# 1_-MCU.net
KiCad netlist of a schematic drawn in Altium Designer
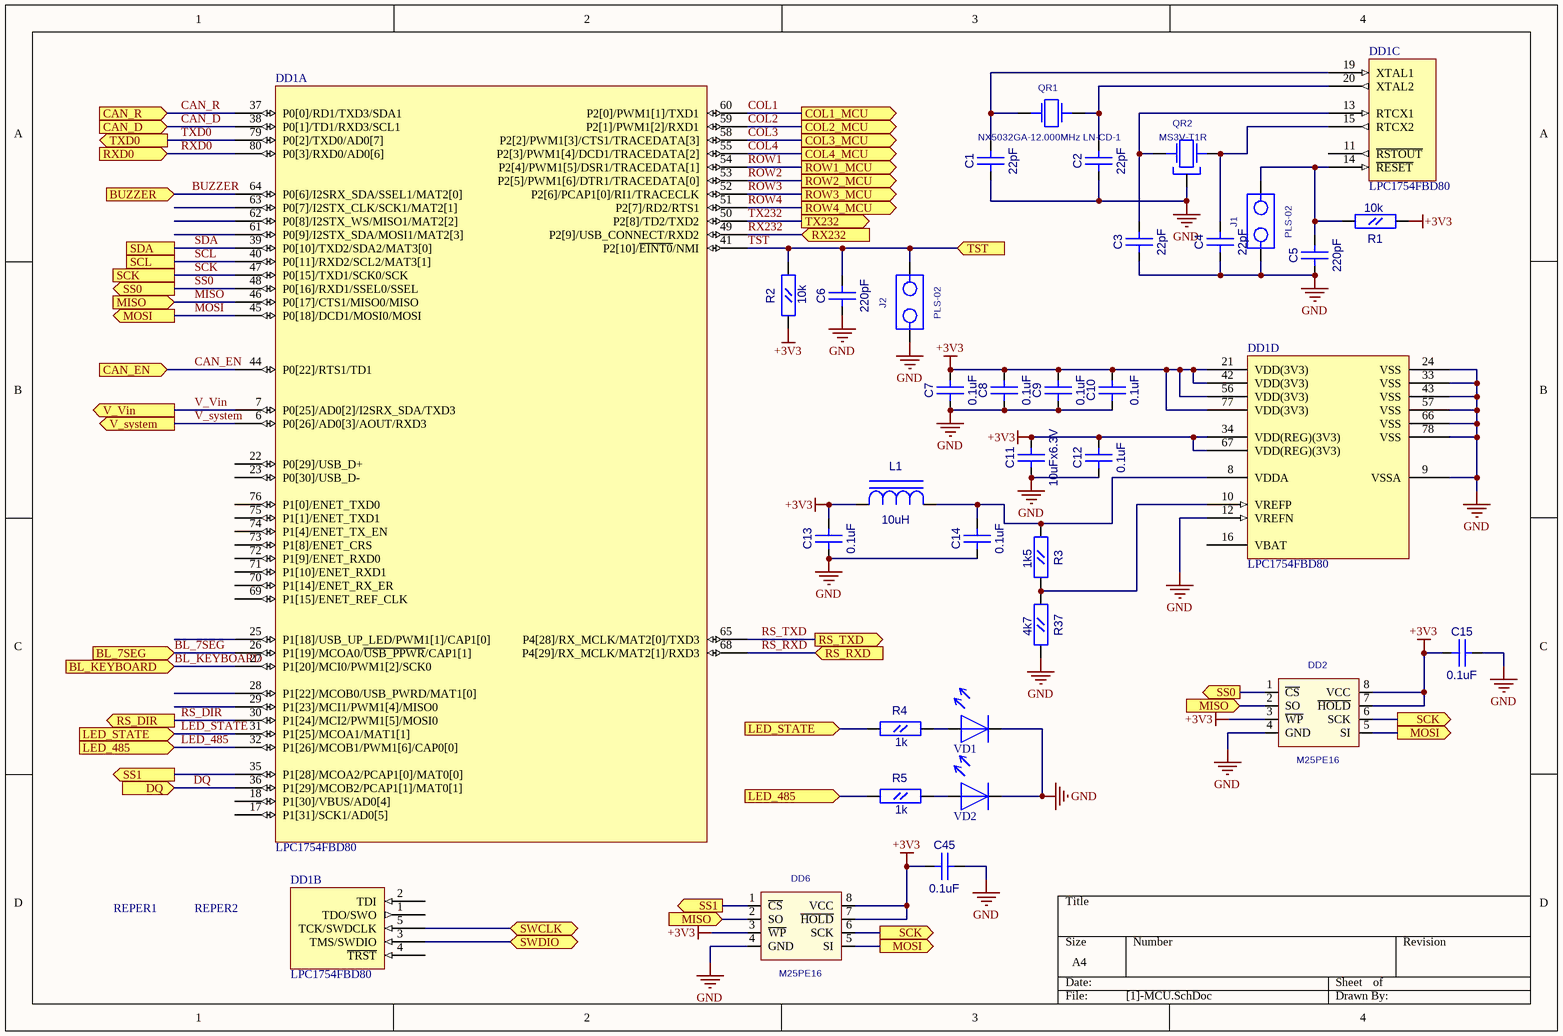
[diagram p0: [1]-MCU.SchDoc]

(export (version "E")
  (design (tool "Eeschema 10.0.6"))
  (components
    (comp (ref "C1")
      (value "22pF")
      (footprint "CC0603")
      (description "CC0603")
      (libsource (lib "gprs_modem_2") (part "CC0603"))
    )
    (comp (ref "C2")
      (value "22pF")
      (footprint "CC0603")
      (description "CC0603")
      (libsource (lib "gprs_modem_2") (part "CC0603"))
    )
    (comp (ref "C3")
      (value "22pF")
      (footprint "CC0603")
      (description "CC0603")
      (libsource (lib "gprs_modem_2") (part "CC0603"))
    )
    (comp (ref "C4")
      (value "22pF")
      (footprint "CC0603")
      (description "CC0603")
      (libsource (lib "gprs_modem_2") (part "CC0603"))
    )
    (comp (ref "C5")
      (value "220pF")
      (footprint "CC0603")
      (description "CC0603")
      (libsource (lib "gprs_modem_2") (part "CC0603"))
    )
    (comp (ref "C6")
      (value "220pF")
      (footprint "CC0603")
      (description "CC0603")
      (libsource (lib "gprs_modem_2") (part "CC0603"))
    )
    (comp (ref "C7")
      (value "0.1uF")
      (footprint "CC0603")
      (description "CC0603")
      (libsource (lib "gprs_modem_2") (part "CC0603"))
    )
    (comp (ref "C8")
      (value "0.1uF")
      (footprint "CC0603")
      (description "CC0603")
      (libsource (lib "gprs_modem_2") (part "CC0603"))
    )
    (comp (ref "C9")
      (value "0.1uF")
      (footprint "CC0603")
      (description "CC0603")
      (libsource (lib "gprs_modem_2") (part "CC0603"))
    )
    (comp (ref "C10")
      (value "0.1uF")
      (footprint "CC0603")
      (description "CC0603")
      (libsource (lib "gprs_modem_2") (part "CC0603"))
    )
    (comp (ref "C11")
      (value "10uFx6.3V")
      (footprint "CC0805")
      (description "CC0805")
      (libsource (lib "gprs_modem_2") (part "CC0805"))
    )
    (comp (ref "C12")
      (value "0.1uF")
      (footprint "CC0603")
      (description "CC0603")
      (libsource (lib "gprs_modem_2") (part "CC0603"))
    )
    (comp (ref "C13")
      (value "0.1uF")
      (footprint "CC0603")
      (description "CC0603")
      (libsource (lib "gprs_modem_2") (part "CC0603"))
    )
    (comp (ref "C14")
      (value "0.1uF")
      (footprint "CC0603")
      (description "CC0603")
      (libsource (lib "gprs_modem_2") (part "CC0603"))
    )
    (comp (ref "C15")
      (value "0.1uF")
      (footprint "CC0603")
      (description "CC0603")
      (libsource (lib "gprs_modem_2") (part "CC0603"))
    )
    (comp (ref "C45")
      (value "0.1uF")
      (footprint "CC0603")
      (description "CC0603")
      (libsource (lib "gprs_modem_2") (part "CC0603"))
    )
    (comp (ref "DD1")
      (value "LPC1754FBD80")
      (footprint "TQFP-80_0.5")
      (description "Cortex -M3 32-Bit Microcontroller, 128KB Flash, 64KB RAM, 800-Lead LQFP")
      (libsource (lib "gprs_modem_2") (part "LPC1754FBD80"))
    )
    (comp (ref "DD2")
      (value "M25PE16")
      (footprint "EIAJ_SO8")
      (description "S25FL016A0LMFI01")
      (libsource (lib "gprs_modem_2") (part "S25FL016A0LMFI01"))
    )
    (comp (ref "DD6")
      (value "M25PE16")
      (footprint "EIAJ_SO8")
      (description "S25FL016A0LMFI01")
      (libsource (lib "gprs_modem_2") (part "S25FL016A0LMFI01"))
    )
    (comp (ref "J1") (value "PLS-02") (footprint "PLS-02") (libsource (lib "gprs_modem_2") (part "PLS-02")))
    (comp (ref "J2") (value "PLS-02") (footprint "PLS-02") (libsource (lib "gprs_modem_2") (part "PLS-02")))
    (comp (ref "L1")
      (value "10uH")
      (footprint "L0603")
      (description "L0603")
      (libsource (lib "gprs_modem_2") (part "L0603"))
    )
    (comp (ref "QR1")
      (value "NX5032GA-12.000MHz LN-CD-1")
      (footprint "AC5032_2")
      (description "AC5032/2")
      (libsource (lib "gprs_modem_2") (part "AC5032_2"))
    )
    (comp (ref "QR2")
      (value "MS3V-T1R")
      (footprint "MS3V-T1R")
      (description "CRYSTAL_32768 Hz")
      (libsource (lib "gprs_modem_2") (part "MS3V-T1R"))
    )
    (comp (ref "R1")
      (value "10k")
      (footprint "RC0603")
      (description "RC0603")
      (libsource (lib "gprs_modem_2") (part "RC0603"))
    )
    (comp (ref "R2")
      (value "10k")
      (footprint "RC0603")
      (description "RC0603")
      (libsource (lib "gprs_modem_2") (part "RC0603"))
    )
    (comp (ref "R3")
      (value "1k5")
      (footprint "RC0603")
      (description "RC0603")
      (libsource (lib "gprs_modem_2") (part "RC0603"))
    )
    (comp (ref "R4")
      (value "1k")
      (footprint "RC0603")
      (description "RC0603")
      (libsource (lib "gprs_modem_2") (part "RC0603"))
    )
    (comp (ref "R5")
      (value "1k")
      (footprint "RC0603")
      (description "RC0603")
      (libsource (lib "gprs_modem_2") (part "RC0603"))
    )
    (comp (ref "R37")
      (value "4k7")
      (footprint "RC0603")
      (description "RC0603")
      (libsource (lib "gprs_modem_2") (part "RC0603"))
    )
    (comp (ref "REPER1")
      (value "REPER1.2")
      (footprint "REPER1.2")
      (libsource (lib "gprs_modem") (part "REPER1.2"))
    )
    (comp (ref "REPER2")
      (value "REPER1.2")
      (footprint "REPER1.2")
      (libsource (lib "gprs_modem") (part "REPER1.2"))
    )
    (comp (ref "VD1")
      (value "LED_0805")
      (footprint "LED0805")
      (libsource (lib "gprs_modem_2") (part "LED_0805"))
    )
    (comp (ref "VD2")
      (value "LED_0805")
      (footprint "LED0805")
      (libsource (lib "gprs_modem_2") (part "LED_0805"))
    )
  )
  (nets
    (net (code "1") (name "+3V3") (class "Default")
      (node (ref "C10") (pin "2") (pinfunction "B_2") (pintype "passive"))
      (node (ref "C11") (pin "2") (pinfunction "B_2") (pintype "passive"))
      (node (ref "C12") (pin "2") (pinfunction "B_2") (pintype "passive"))
      (node (ref "C13") (pin "2") (pinfunction "B_2") (pintype "passive"))
      (node (ref "C15") (pin "1") (pinfunction "A_1") (pintype "passive"))
      (node (ref "C45") (pin "1") (pinfunction "A_1") (pintype "passive"))
      (node (ref "C7") (pin "2") (pinfunction "B_2") (pintype "passive"))
      (node (ref "C8") (pin "2") (pinfunction "B_2") (pintype "passive"))
      (node (ref "C9") (pin "2") (pinfunction "B_2") (pintype "passive"))
      (node (ref "DD1") (pin "21") (pinfunction "VDD(3V3)_21") (pintype "power_in"))
      (node (ref "DD1") (pin "34") (pinfunction "VDD(REG)(3V3)_34") (pintype "power_in"))
      (node (ref "DD1") (pin "42") (pinfunction "VDD(3V3)_42") (pintype "power_in"))
      (node (ref "DD1") (pin "56") (pinfunction "VDD(3V3)_56") (pintype "power_in"))
      (node (ref "DD1") (pin "67") (pinfunction "VDD(REG)(3V3)_67") (pintype "power_in"))
      (node (ref "DD1") (pin "77") (pinfunction "VDD(3V3)_77") (pintype "power_in"))
      (node (ref "DD2") (pin "3") (pinfunction "~{WP}_3") (pintype "passive"))
      (node (ref "DD2") (pin "7") (pinfunction "~{HOLD}_7") (pintype "passive"))
      (node (ref "DD2") (pin "8") (pinfunction "VCC_8") (pintype "passive"))
      (node (ref "DD6") (pin "3") (pinfunction "~{WP}_3") (pintype "passive"))
      (node (ref "DD6") (pin "7") (pinfunction "~{HOLD}_7") (pintype "passive"))
      (node (ref "DD6") (pin "8") (pinfunction "VCC_8") (pintype "passive"))
      (node (ref "L1") (pin "1") (pinfunction "A_1") (pintype "passive"))
      (node (ref "R1") (pin "1") (pinfunction "A_1") (pintype "passive"))
      (node (ref "R2") (pin "1") (pinfunction "A_1") (pintype "passive"))
    )
    (net (code "2") (name "/BL_7SEG") (class "Default")
      (node (ref "DD1") (pin "26") (pinfunction "P1[19]/MCOA0/~{USB_PPWR}/CAP1[1]_26") (pintype "bidirectional"))
    )
    (net (code "3") (name "/BL_KEYBOARD") (class "Default")
      (node (ref "DD1") (pin "27") (pinfunction "P1[20]/MCI0/PWM1[2]/SCK0_27") (pintype "bidirectional"))
    )
    (net (code "4") (name "/BUZZER") (class "Default")
      (node (ref "DD1") (pin "64") (pinfunction "P0[6]/I2SRX_SDA/SSEL1/MAT2[0]_64") (pintype "bidirectional"))
    )
    (net (code "5") (name "/CAN_D") (class "Default")
      (node (ref "DD1") (pin "38") (pinfunction "P0[1]/TD1/RXD3/SCL1_38") (pintype "bidirectional"))
    )
    (net (code "6") (name "/CAN_EN") (class "Default")
      (node (ref "DD1") (pin "44") (pinfunction "P0[22]/RTS1/TD1_44") (pintype "bidirectional"))
    )
    (net (code "7") (name "/CAN_R") (class "Default")
      (node (ref "DD1") (pin "37") (pinfunction "P0[0]/RD1/TXD3/SDA1_37") (pintype "bidirectional"))
    )
    (net (code "8") (name "/COL1") (class "Default")
      (node (ref "DD1") (pin "60") (pinfunction "P2[0]/PWM1[1]/TXD1_60") (pintype "bidirectional"))
    )
    (net (code "9") (name "/COL2") (class "Default")
      (node (ref "DD1") (pin "59") (pinfunction "P2[1]/PWM1[2]/RXD1_59") (pintype "bidirectional"))
    )
    (net (code "10") (name "/COL3") (class "Default")
      (node (ref "DD1") (pin "58") (pinfunction "P2[2]/PWM1[3]/CTS1/TRACEDATA[3]_58") (pintype "bidirectional"))
    )
    (net (code "11") (name "/COL4") (class "Default")
      (node (ref "DD1") (pin "55") (pinfunction "P2[3]/PWM1[4]/DCD1/TRACEDATA[2]_55") (pintype "bidirectional"))
    )
    (net (code "12") (name "/DQ") (class "Default")
      (node (ref "DD1") (pin "36") (pinfunction "P1[29]/MCOB2/PCAP1[1]/MAT0[1]_36") (pintype "bidirectional"))
    )
    (net (code "13") (name "/LED_485") (class "Default")
      (node (ref "DD1") (pin "32") (pinfunction "P1[26]/MCOB1/PWM1[6]/CAP0[0]_32") (pintype "bidirectional"))
      (node (ref "R5") (pin "1") (pinfunction "A_1") (pintype "passive"))
    )
    (net (code "14") (name "/LED_STATE") (class "Default")
      (node (ref "DD1") (pin "31") (pinfunction "P1[25]/MCOA1/MAT1[1]_31") (pintype "bidirectional"))
      (node (ref "R4") (pin "1") (pinfunction "A_1") (pintype "passive"))
    )
    (net (code "15") (name "/MISO") (class "Default")
      (node (ref "DD1") (pin "46") (pinfunction "P0[17]/CTS1/MISO0/MISO_46") (pintype "bidirectional"))
      (node (ref "DD2") (pin "2") (pinfunction "SO_2") (pintype "passive"))
      (node (ref "DD6") (pin "2") (pinfunction "SO_2") (pintype "passive"))
    )
    (net (code "16") (name "/MOSI") (class "Default")
      (node (ref "DD1") (pin "45") (pinfunction "P0[18]/DCD1/MOSI0/MOSI_45") (pintype "bidirectional"))
      (node (ref "DD2") (pin "5") (pinfunction "SI_5") (pintype "passive"))
      (node (ref "DD6") (pin "5") (pinfunction "SI_5") (pintype "passive"))
    )
    (net (code "17") (name "/ROW1") (class "Default")
      (node (ref "DD1") (pin "54") (pinfunction "P2[4]/PWM1[5]/DSR1/TRACEDATA[1]_54") (pintype "bidirectional"))
    )
    (net (code "18") (name "/ROW2") (class "Default")
      (node (ref "DD1") (pin "53") (pinfunction "P2[5]/PWM1[6]/DTR1/TRACEDATA[0]_53") (pintype "bidirectional"))
    )
    (net (code "19") (name "/ROW3") (class "Default")
      (node (ref "DD1") (pin "52") (pinfunction "P2[6]/PCAP1[0]/RI1/TRACECLK_52") (pintype "bidirectional"))
    )
    (net (code "20") (name "/ROW4") (class "Default")
      (node (ref "DD1") (pin "51") (pinfunction "P2[7]/RD2/RTS1_51") (pintype "bidirectional"))
    )
    (net (code "21") (name "/RS_DIR") (class "Default")
      (node (ref "DD1") (pin "30") (pinfunction "P1[24]/MCI2/PWM1[5]/MOSI0_30") (pintype "bidirectional"))
    )
    (net (code "22") (name "/RS_RXD") (class "Default")
      (node (ref "DD1") (pin "68") (pinfunction "P4[29]/RX_MCLK/MAT2[1]/RXD3_68") (pintype "bidirectional"))
    )
    (net (code "23") (name "/RS_TXD") (class "Default")
      (node (ref "DD1") (pin "65") (pinfunction "P4[28]/RX_MCLK/MAT2[0]/TXD3_65") (pintype "bidirectional"))
    )
    (net (code "24") (name "/RX232") (class "Default")
      (node (ref "DD1") (pin "49") (pinfunction "P2[9]/USB_CONNECT/RXD2_49") (pintype "bidirectional"))
    )
    (net (code "25") (name "/RXD0") (class "Default")
      (node (ref "DD1") (pin "80") (pinfunction "P0[3]/RXD0/AD0[6]_80") (pintype "bidirectional"))
    )
    (net (code "26") (name "/SCK") (class "Default")
      (node (ref "DD1") (pin "47") (pinfunction "P0[15]/TXD1/SCK0/SCK_47") (pintype "bidirectional"))
      (node (ref "DD2") (pin "6") (pinfunction "SCK_6") (pintype "passive"))
      (node (ref "DD6") (pin "6") (pinfunction "SCK_6") (pintype "passive"))
    )
    (net (code "27") (name "/SCL") (class "Default")
      (node (ref "DD1") (pin "40") (pinfunction "P0[11]/RXD2/SCL2/MAT3[1]_40") (pintype "bidirectional"))
    )
    (net (code "28") (name "/SDA") (class "Default")
      (node (ref "DD1") (pin "39") (pinfunction "P0[10]/TXD2/SDA2/MAT3[0]_39") (pintype "bidirectional"))
    )
    (net (code "29") (name "/SS0") (class "Default")
      (node (ref "DD1") (pin "48") (pinfunction "P0[16]/RXD1/SSEL0/SSEL_48") (pintype "bidirectional"))
      (node (ref "DD2") (pin "1") (pinfunction "~{CS}_1") (pintype "passive"))
    )
    (net (code "30") (name "/SS1") (class "Default")
      (node (ref "DD1") (pin "35") (pinfunction "P1[28]/MCOA2/PCAP1[0]/MAT0[0]_35") (pintype "bidirectional"))
      (node (ref "DD6") (pin "1") (pinfunction "~{CS}_1") (pintype "passive"))
    )
    (net (code "31") (name "/SWCLK") (class "Default")
      (node (ref "DD1") (pin "5") (pinfunction "TCK/SWDCLK_5") (pintype "input"))
    )
    (net (code "32") (name "/SWDIO") (class "Default")
      (node (ref "DD1") (pin "3") (pinfunction "TMS/SWDIO_3") (pintype "input"))
    )
    (net (code "33") (name "/TST") (class "Default")
      (node (ref "C6") (pin "2") (pinfunction "B_2") (pintype "passive"))
      (node (ref "DD1") (pin "41") (pinfunction "P2[10]/~{EINT0}/NMI_41") (pintype "bidirectional"))
      (node (ref "J2") (pin "2") (pintype "passive"))
      (node (ref "R2") (pin "2") (pinfunction "B_2") (pintype "passive"))
    )
    (net (code "34") (name "/TX232") (class "Default")
      (node (ref "DD1") (pin "50") (pinfunction "P2[8]/TD2/TXD2_50") (pintype "bidirectional"))
    )
    (net (code "35") (name "/TXD0") (class "Default")
      (node (ref "DD1") (pin "79") (pinfunction "P0[2]/TXD0/AD0[7]_79") (pintype "bidirectional"))
    )
    (net (code "36") (name "/V_Vin") (class "Default")
      (node (ref "DD1") (pin "7") (pinfunction "P0[25]/AD0[2]/I2SRX_SDA/TXD3_7") (pintype "bidirectional"))
    )
    (net (code "37") (name "/V_system") (class "Default")
      (node (ref "DD1") (pin "6") (pinfunction "P0[26]/AD0[3]/AOUT/RXD3_6") (pintype "bidirectional"))
    )
    (net (code "38") (name "GND") (class "Default")
      (node (ref "C1") (pin "1") (pinfunction "A_1") (pintype "passive"))
      (node (ref "C10") (pin "1") (pinfunction "A_1") (pintype "passive"))
      (node (ref "C11") (pin "1") (pinfunction "A_1") (pintype "passive"))
      (node (ref "C12") (pin "1") (pinfunction "A_1") (pintype "passive"))
      (node (ref "C13") (pin "1") (pinfunction "A_1") (pintype "passive"))
      (node (ref "C14") (pin "1") (pinfunction "A_1") (pintype "passive"))
      (node (ref "C15") (pin "2") (pinfunction "B_2") (pintype "passive"))
      (node (ref "C2") (pin "1") (pinfunction "A_1") (pintype "passive"))
      (node (ref "C3") (pin "1") (pinfunction "A_1") (pintype "passive"))
      (node (ref "C4") (pin "1") (pinfunction "A_1") (pintype "passive"))
      (node (ref "C45") (pin "2") (pinfunction "B_2") (pintype "passive"))
      (node (ref "C5") (pin "1") (pinfunction "A_1") (pintype "passive"))
      (node (ref "C6") (pin "1") (pinfunction "A_1") (pintype "passive"))
      (node (ref "C7") (pin "1") (pinfunction "A_1") (pintype "passive"))
      (node (ref "C8") (pin "1") (pinfunction "A_1") (pintype "passive"))
      (node (ref "C9") (pin "1") (pinfunction "A_1") (pintype "passive"))
      (node (ref "DD1") (pin "12") (pinfunction "VREFN_12") (pintype "input"))
      (node (ref "DD1") (pin "24") (pinfunction "VSS_24") (pintype "power_in"))
      (node (ref "DD1") (pin "33") (pinfunction "VSS_33") (pintype "power_in"))
      (node (ref "DD1") (pin "43") (pinfunction "VSS_43") (pintype "power_in"))
      (node (ref "DD1") (pin "57") (pinfunction "VSS_57") (pintype "power_in"))
      (node (ref "DD1") (pin "66") (pinfunction "VSS_66") (pintype "power_in"))
      (node (ref "DD1") (pin "78") (pinfunction "VSS_78") (pintype "power_in"))
      (node (ref "DD1") (pin "9") (pinfunction "VSSA_9") (pintype "power_in"))
      (node (ref "DD2") (pin "4") (pinfunction "GND_4") (pintype "passive"))
      (node (ref "DD6") (pin "4") (pinfunction "GND_4") (pintype "passive"))
      (node (ref "J1") (pin "1") (pintype "passive"))
      (node (ref "J2") (pin "1") (pintype "passive"))
      (node (ref "QR2") (pin "3") (pinfunction "3_3") (pintype "passive"))
      (node (ref "R37") (pin "2") (pinfunction "B_2") (pintype "passive"))
      (node (ref "VD1") (pin "2") (pintype "passive"))
      (node (ref "VD2") (pin "2") (pintype "passive"))
    )
    (net (code "39") (name "Net-(C1-B)") (class "Default")
      (node (ref "C1") (pin "2") (pinfunction "B_2") (pintype "passive"))
      (node (ref "DD1") (pin "19") (pinfunction "XTAL1_19") (pintype "input"))
      (node (ref "QR1") (pin "1") (pintype "passive"))
    )
    (net (code "40") (name "Net-(C2-B)") (class "Default")
      (node (ref "C2") (pin "2") (pinfunction "B_2") (pintype "passive"))
      (node (ref "DD1") (pin "20") (pinfunction "XTAL2_20") (pintype "output"))
      (node (ref "QR1") (pin "2") (pintype "passive"))
    )
    (net (code "41") (name "Net-(C3-B)") (class "Default")
      (node (ref "C3") (pin "2") (pinfunction "B_2") (pintype "passive"))
      (node (ref "DD1") (pin "13") (pinfunction "RTCX1_13") (pintype "input"))
      (node (ref "QR2") (pin "2") (pinfunction "X2_2") (pintype "passive"))
    )
    (net (code "42") (name "Net-(C4-B)") (class "Default")
      (node (ref "C4") (pin "2") (pinfunction "B_2") (pintype "passive"))
      (node (ref "DD1") (pin "15") (pinfunction "RTCX2_15") (pintype "output"))
      (node (ref "QR2") (pin "1") (pinfunction "X1_1") (pintype "passive"))
    )
    (net (code "43") (name "Net-(C5-B)") (class "Default")
      (node (ref "C5") (pin "2") (pinfunction "B_2") (pintype "passive"))
      (node (ref "DD1") (pin "14") (pinfunction "~{RESET}_14") (pintype "input"))
      (node (ref "J1") (pin "2") (pintype "passive"))
      (node (ref "R1") (pin "2") (pinfunction "B_2") (pintype "passive"))
    )
    (net (code "44") (name "Net-(C14-B)") (class "Default")
      (node (ref "C14") (pin "2") (pinfunction "B_2") (pintype "passive"))
      (node (ref "DD1") (pin "8") (pinfunction "VDDA_8") (pintype "power_in"))
      (node (ref "L1") (pin "2") (pinfunction "C_2") (pintype "passive"))
      (node (ref "R3") (pin "1") (pinfunction "A_1") (pintype "passive"))
    )
    (net (code "45") (name "Net-(DD1D-VREFP)") (class "Default")
      (node (ref "DD1") (pin "10") (pinfunction "VREFP_10") (pintype "input"))
      (node (ref "R3") (pin "2") (pinfunction "B_2") (pintype "passive"))
      (node (ref "R37") (pin "1") (pinfunction "A_1") (pintype "passive"))
    )
    (net (code "46") (name "Net-(R4-B)") (class "Default")
      (node (ref "R4") (pin "2") (pinfunction "B_2") (pintype "passive"))
      (node (ref "VD1") (pin "1") (pintype "passive"))
    )
    (net (code "47") (name "Net-(R5-B)") (class "Default")
      (node (ref "R5") (pin "2") (pinfunction "B_2") (pintype "passive"))
      (node (ref "VD2") (pin "1") (pintype "passive"))
    )
    (net (code "48") (name "unconnected-(DD1A-P0[7]{slash}I2STX_CLK{slash}SCK1{slash}MAT2[1]-Pad63)") (class "Default")
      (node (ref "DD1") (pin "63") (pinfunction "P0[7]/I2STX_CLK/SCK1/MAT2[1]_63") (pintype "bidirectional"))
    )
    (net (code "49") (name "unconnected-(DD1A-P0[8]{slash}I2STX_WS{slash}MISO1{slash}MAT2[2]-Pad62)") (class "Default")
      (node (ref "DD1") (pin "62") (pinfunction "P0[8]/I2STX_WS/MISO1/MAT2[2]_62") (pintype "bidirectional"))
    )
    (net (code "50") (name "unconnected-(DD1A-P0[9]{slash}I2STX_SDA{slash}MOSI1{slash}MAT2[3]-Pad61)") (class "Default")
      (node (ref "DD1") (pin "61") (pinfunction "P0[9]/I2STX_SDA/MOSI1/MAT2[3]_61") (pintype "bidirectional"))
    )
    (net (code "51") (name "unconnected-(DD1A-P0[29]{slash}USB_D+-Pad22)") (class "Default")
      (node (ref "DD1") (pin "22") (pinfunction "P0[29]/USB_D+_22") (pintype "bidirectional"))
    )
    (net (code "52") (name "unconnected-(DD1A-P0[30]{slash}USB_D--Pad23)") (class "Default")
      (node (ref "DD1") (pin "23") (pinfunction "P0[30]/USB_D-_23") (pintype "bidirectional"))
    )
    (net (code "53") (name "unconnected-(DD1A-P1[0]{slash}ENET_TXD0-Pad76)") (class "Default")
      (node (ref "DD1") (pin "76") (pinfunction "P1[0]/ENET_TXD0_76") (pintype "bidirectional"))
    )
    (net (code "54") (name "unconnected-(DD1A-P1[1]{slash}ENET_TXD1-Pad75)") (class "Default")
      (node (ref "DD1") (pin "75") (pinfunction "P1[1]/ENET_TXD1_75") (pintype "bidirectional"))
    )
    (net (code "55") (name "unconnected-(DD1A-P1[4]{slash}ENET_TX_EN-Pad74)") (class "Default")
      (node (ref "DD1") (pin "74") (pinfunction "P1[4]/ENET_TX_EN_74") (pintype "bidirectional"))
    )
    (net (code "56") (name "unconnected-(DD1A-P1[8]{slash}ENET_CRS-Pad73)") (class "Default")
      (node (ref "DD1") (pin "73") (pinfunction "P1[8]/ENET_CRS_73") (pintype "bidirectional"))
    )
    (net (code "57") (name "unconnected-(DD1A-P1[9]{slash}ENET_RXD0-Pad72)") (class "Default")
      (node (ref "DD1") (pin "72") (pinfunction "P1[9]/ENET_RXD0_72") (pintype "bidirectional"))
    )
    (net (code "58") (name "unconnected-(DD1A-P1[10]{slash}ENET_RXD1-Pad71)") (class "Default")
      (node (ref "DD1") (pin "71") (pinfunction "P1[10]/ENET_RXD1_71") (pintype "bidirectional"))
    )
    (net (code "59") (name "unconnected-(DD1A-P1[14]{slash}ENET_RX_ER-Pad70)") (class "Default")
      (node (ref "DD1") (pin "70") (pinfunction "P1[14]/ENET_RX_ER_70") (pintype "bidirectional"))
    )
    (net (code "60") (name "unconnected-(DD1A-P1[15]{slash}ENET_REF_CLK-Pad69)") (class "Default")
      (node (ref "DD1") (pin "69") (pinfunction "P1[15]/ENET_REF_CLK_69") (pintype "bidirectional"))
    )
    (net (code "61") (name "unconnected-(DD1A-P1[18]{slash}USB_UP_LED{slash}PWM1[1]{slash}CAP1[0]-Pad25)") (class "Default")
      (node (ref "DD1") (pin "25") (pinfunction "P1[18]/USB_UP_LED/PWM1[1]/CAP1[0]_25") (pintype "bidirectional"))
    )
    (net (code "62") (name "unconnected-(DD1A-P1[22]{slash}MCOB0{slash}USB_PWRD{slash}MAT1[0]-Pad28)") (class "Default")
      (node (ref "DD1") (pin "28") (pinfunction "P1[22]/MCOB0/USB_PWRD/MAT1[0]_28") (pintype "bidirectional"))
    )
    (net (code "63") (name "unconnected-(DD1A-P1[23]{slash}MCI1{slash}PWM1[4]{slash}MISO0-Pad29)") (class "Default")
      (node (ref "DD1") (pin "29") (pinfunction "P1[23]/MCI1/PWM1[4]/MISO0_29") (pintype "bidirectional"))
    )
    (net (code "64") (name "unconnected-(DD1A-P1[30]{slash}VBUS{slash}AD0[4]-Pad18)") (class "Default")
      (node (ref "DD1") (pin "18") (pinfunction "P1[30]/VBUS/AD0[4]_18") (pintype "bidirectional"))
    )
    (net (code "65") (name "unconnected-(DD1A-P1[31]{slash}SCK1{slash}AD0[5]-Pad17)") (class "Default")
      (node (ref "DD1") (pin "17") (pinfunction "P1[31]/SCK1/AD0[5]_17") (pintype "bidirectional"))
    )
    (net (code "66") (name "unconnected-(DD1B-TDI-Pad2)") (class "Default")
      (node (ref "DD1") (pin "2") (pinfunction "TDI_2") (pintype "input"))
    )
    (net (code "67") (name "unconnected-(DD1B-TDO{slash}SWO-Pad1)") (class "Default")
      (node (ref "DD1") (pin "1") (pinfunction "TDO/SWO_1") (pintype "output"))
    )
    (net (code "68") (name "unconnected-(DD1B-~{TRST}-Pad4)") (class "Default")
      (node (ref "DD1") (pin "4") (pinfunction "~{TRST}_4") (pintype "input"))
    )
    (net (code "69") (name "unconnected-(DD1C-~{RSTOUT}-Pad11)") (class "Default")
      (node (ref "DD1") (pin "11") (pinfunction "~{RSTOUT}_11") (pintype "output"))
    )
    (net (code "70") (name "unconnected-(DD1D-VBAT-Pad16)") (class "Default")
      (node (ref "DD1") (pin "16") (pinfunction "VBAT_16") (pintype "power_in"))
    )
    (net (code "71") (name "unconnected-(REPER1-Pad1)") (class "Default")
      (node (ref "REPER1") (pin "1") (pintype "passive"))
    )
    (net (code "72") (name "unconnected-(REPER2-Pad1)") (class "Default")
      (node (ref "REPER2") (pin "1") (pintype "passive"))
    )
  )
)
